# DiodeBoard.net
KiCad netlist of a schematic drawn in EAGLE
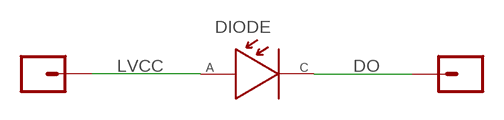
[diagram p0: schematic, sheet 1]

(export (version "E")
  (design (tool "Eeschema 10.0.6"))
  (components
    (comp (ref "DI")
      (value "SINGLE-THROUGH-HOLE")
      (footprint "eagle-import:SINGLE-THROUGH-HOLE")
      (libsource (lib "eagle-import") (part "SINGLE-THROUGH-HOLE"))
    )
    (comp (ref "DIODE")
      (value "PHOTODIODEBPW")
      (footprint "eagle-import:BPW34_BP104_SMD")
      (libsource (lib "eagle-import") (part "PHOTODIODEBPW"))
    )
    (comp (ref "DO")
      (value "SINGLE-THROUGH-HOLE")
      (footprint "eagle-import:SINGLE-THROUGH-HOLE")
      (libsource (lib "eagle-import") (part "SINGLE-THROUGH-HOLE"))
    )
  )
  (nets
    (net (code "1") (name "/DO") (class "Default")
      (node (ref "DIODE") (pin "CATHODE") (pinfunction "CATHODE_CATHODE") (pintype "bidirectional"))
      (node (ref "DO") (pin "1") (pinfunction "1_1") (pintype "passive"))
    )
    (net (code "2") (name "/LVCC") (class "Default")
      (node (ref "DI") (pin "1") (pinfunction "1_1") (pintype "passive"))
      (node (ref "DIODE") (pin "ANODE") (pinfunction "ANODE_ANODE") (pintype "bidirectional"))
    )
  )
)
